# led_RGB_esp32_schematic.net
KiCad netlist of a schematic drawn in Altium Designer
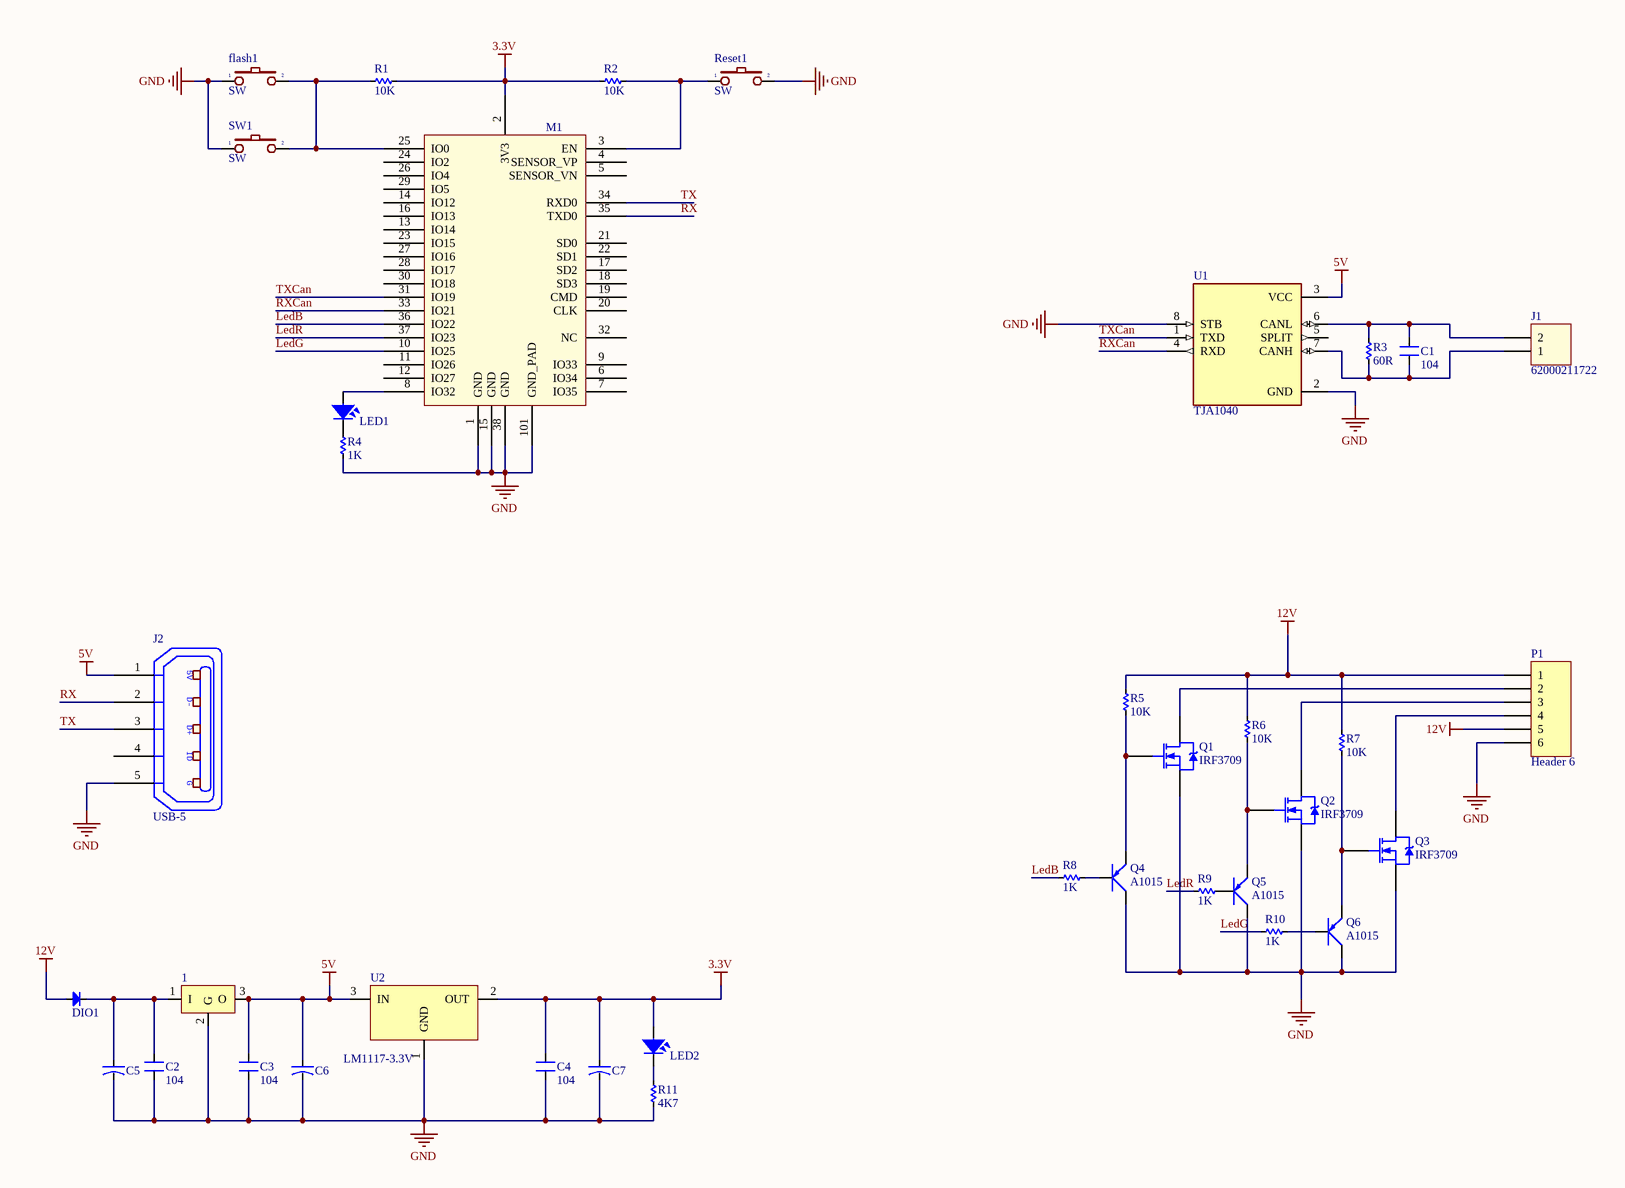
[diagram p0: led_RGB_esp32_schematic.SchDoc]

(export (version "E")
  (design (tool "Eeschema 10.0.6"))
  (components
    (comp (ref "1")
      (value "LM78xx")
      (footprint "TO252-123")
      (description "Positive Voltage Regulator")
      (fields (field (name "PUBLISHER") "Altium Limited"))
      (libsource (lib "LIBRARY") (part "LM78xx"))
    )
    (comp (ref "C1")
      (value "104")
      (footprint "SM-CAP-0805")
      (fields (field (name "DESIGNED BY") "VanDungEvn"))
      (libsource (lib "electronicvn-library1") (part "CN"))
    )
    (comp (ref "C2")
      (value "104")
      (footprint "SM-CAP-0805")
      (fields (field (name "DESIGNED BY") "VanDungEvn"))
      (libsource (lib "electronicvn-library1") (part "CN"))
    )
    (comp (ref "C3")
      (value "104")
      (footprint "SM-CAP-0805")
      (fields (field (name "DESIGNED BY") "VanDungEvn"))
      (libsource (lib "electronicvn-library1") (part "CN"))
    )
    (comp (ref "C4")
      (value "104")
      (footprint "SM-CAP-0805")
      (fields (field (name "DESIGNED BY") "VanDungEvn"))
      (libsource (lib "electronicvn-library1") (part "CN"))
    )
    (comp (ref "C5")
      (value "CN-ALU-SMD")
      (footprint "CAP-ALU-SMD-4.5x5x1.4")
      (description "Polarized Capacitor (Axial)")
      (fields (field (name "PUBLISHER") "Altium Limited"))
      (libsource (lib "LIBTanCN") (part "CN-ALU-SMD"))
    )
    (comp (ref "C6")
      (value "CN-ALU-SMD")
      (footprint "CAP-ALU-SMD-4.5x5x1.4")
      (description "Polarized Capacitor (Axial)")
      (fields (field (name "PUBLISHER") "Altium Limited"))
      (libsource (lib "LIBTanCN") (part "CN-ALU-SMD"))
    )
    (comp (ref "C7")
      (value "CN-ALU-SMD")
      (footprint "CAP-ALU-SMD-4.5x5x1.4")
      (description "Polarized Capacitor (Axial)")
      (fields (field (name "PUBLISHER") "Altium Limited"))
      (libsource (lib "LIBTanCN") (part "CN-ALU-SMD"))
    )
    (comp (ref "DIO1")
      (value "Diode SMD")
      (footprint "DIO-SMD-106")
      (description "Default Diode")
      (fields (field (name "PUBLISHER") "Altium Limited"))
      (libsource (lib "LIBRARY") (part "Diode SMD"))
    )
    (comp (ref "flash1")
      (value "SW")
      (footprint "SW-DIP1-1")
      (description "Switch button 2 pin")
      (libsource (lib "LIBRARY") (part "SW2"))
    )
    (comp (ref "J1")
      (value "62000211722")
      (footprint "62000211722")
      (description "WR-WTB 2.00mm Male Horizontal Shrouded Header, 2p")
      (fields (field (name "PUBLISHER") "Wurth Elektronik"))
      (libsource (lib "Header2.0") (part "62000211722"))
    )
    (comp (ref "J2")
      (value "USB-5")
      (footprint "USB-M1")
      (fields
        (field (name "MANUFACTURER") "FCI")
        (field (name "MANUFACTURER PART NUMBER") "10118193-0001LF")
        (field (name ".CREATOR") "MM")
        (field (name ".CHECKED PCB") "RF")
        (field (name ".CHECKED SCH") "MM")
      )
      (libsource (lib "LIBRARY") (part "USB-5"))
    )
    (comp (ref "LED1") (value "LED") (footprint "LED-0805-Blue") (libsource (lib "LIBRARY") (part "LED SMD")))
    (comp (ref "LED2") (value "LED") (footprint "LED-0805-Blue") (libsource (lib "LIBRARY") (part "LED SMD")))
    (comp (ref "M1")
      (value "ESP32S_Module")
      (footprint "ESP32S")
      (description "Esp-32S")
      (libsource (lib "ESP32S") (part "ESP32S_Module"))
    )
    (comp (ref "P1")
      (value "Header 6")
      (footprint "HED6T")
      (description "Header, 6-Pin")
      (fields (field (name "PUBLISHER") "Altium Limited"))
      (libsource (lib "LIBTanCN") (part "Header 6"))
    )
    (comp (ref "Q1")
      (value "IRF3709")
      (footprint "D2PAK_N")
      (description "HEXFET N-Channel Power MOSFET")
      (fields (field (name "PUBLISHER") "Altium Limited"))
      (libsource (lib "IR Discrete MOSFET - Power") (part "IRF540S"))
    )
    (comp (ref "Q2")
      (value "IRF3709")
      (footprint "D2PAK_N")
      (description "HEXFET N-Channel Power MOSFET")
      (fields (field (name "PUBLISHER") "Altium Limited"))
      (libsource (lib "IR Discrete MOSFET - Power") (part "IRF540S"))
    )
    (comp (ref "Q3")
      (value "IRF3709")
      (footprint "D2PAK_N")
      (description "HEXFET N-Channel Power MOSFET")
      (fields (field (name "PUBLISHER") "Altium Limited"))
      (libsource (lib "IR Discrete MOSFET - Power") (part "IRF540S"))
    )
    (comp (ref "Q4")
      (value "A1015")
      (footprint "SOT23B")
      (description "PNP 600mW, ECB")
      (libsource (lib "electronicvn-library1") (part "A1015"))
    )
    (comp (ref "Q5")
      (value "A1015")
      (footprint "SOT23B")
      (description "PNP 600mW, ECB")
      (libsource (lib "electronicvn-library1") (part "A1015"))
    )
    (comp (ref "Q6")
      (value "A1015")
      (footprint "SOT23B")
      (description "PNP 600mW, ECB")
      (libsource (lib "electronicvn-library1") (part "A1015"))
    )
    (comp (ref "R1")
      (value "10K")
      (footprint "RES-SMD-0805")
      (description "Resistor")
      (fields
        (field (name "MANUFACTURER") "Generic Components")
        (field (name "PUBLISHER") "Altium Hobart Technology Centre")
      )
      (libsource (lib "LIBRARY") (part "Res-SMD"))
    )
    (comp (ref "R2")
      (value "10K")
      (footprint "RES-SMD-0805")
      (description "Resistor")
      (fields
        (field (name "MANUFACTURER") "Generic Components")
        (field (name "PUBLISHER") "Altium Hobart Technology Centre")
      )
      (libsource (lib "LIBRARY") (part "Res-SMD"))
    )
    (comp (ref "R3")
      (value "60R")
      (footprint "RES-SMD-0805")
      (description "Resistor")
      (fields
        (field (name "MANUFACTURER") "Generic Components")
        (field (name "PUBLISHER") "Altium Hobart Technology Centre")
      )
      (libsource (lib "LIBRARY") (part "Res-SMD"))
    )
    (comp (ref "R4")
      (value "1K")
      (footprint "RES-SMD-0805")
      (description "Resistor")
      (fields
        (field (name "MANUFACTURER") "Generic Components")
        (field (name "PUBLISHER") "Altium Hobart Technology Centre")
      )
      (libsource (lib "LIBRARY") (part "Res-SMD"))
    )
    (comp (ref "R5")
      (value "10K")
      (footprint "RES-SMD-0805")
      (description "Resistor")
      (fields
        (field (name "MANUFACTURER") "Generic Components")
        (field (name "PUBLISHER") "Altium Hobart Technology Centre")
      )
      (libsource (lib "LIBRARY") (part "Res-SMD"))
    )
    (comp (ref "R6")
      (value "10K")
      (footprint "RES-SMD-0805")
      (description "Resistor")
      (fields
        (field (name "MANUFACTURER") "Generic Components")
        (field (name "PUBLISHER") "Altium Hobart Technology Centre")
      )
      (libsource (lib "LIBRARY") (part "Res-SMD"))
    )
    (comp (ref "R7")
      (value "10K")
      (footprint "RES-SMD-0805")
      (description "Resistor")
      (fields
        (field (name "MANUFACTURER") "Generic Components")
        (field (name "PUBLISHER") "Altium Hobart Technology Centre")
      )
      (libsource (lib "LIBRARY") (part "Res-SMD"))
    )
    (comp (ref "R8")
      (value "1K")
      (footprint "RES-SMD-0805")
      (description "Resistor")
      (fields
        (field (name "MANUFACTURER") "Generic Components")
        (field (name "PUBLISHER") "Altium Hobart Technology Centre")
      )
      (libsource (lib "LIBRARY") (part "Res-SMD"))
    )
    (comp (ref "R9")
      (value "1K")
      (footprint "RES-SMD-0805")
      (description "Resistor")
      (fields
        (field (name "MANUFACTURER") "Generic Components")
        (field (name "PUBLISHER") "Altium Hobart Technology Centre")
      )
      (libsource (lib "LIBRARY") (part "Res-SMD"))
    )
    (comp (ref "R10")
      (value "1K")
      (footprint "RES-SMD-0805")
      (description "Resistor")
      (fields
        (field (name "MANUFACTURER") "Generic Components")
        (field (name "PUBLISHER") "Altium Hobart Technology Centre")
      )
      (libsource (lib "LIBRARY") (part "Res-SMD"))
    )
    (comp (ref "R11")
      (value "4K7")
      (footprint "RES-SMD-0805")
      (description "Resistor")
      (fields
        (field (name "MANUFACTURER") "Generic Components")
        (field (name "PUBLISHER") "Altium Hobart Technology Centre")
      )
      (libsource (lib "LIBRARY") (part "Res-SMD"))
    )
    (comp (ref "Reset1")
      (value "SW")
      (footprint "SW1-SMD")
      (description "Switch button 2 pin")
      (libsource (lib "LIBRARY") (part "SW2"))
    )
    (comp (ref "SW1")
      (value "SW")
      (footprint "SW2-D2")
      (description "Switch button 2 pin")
      (libsource (lib "LIBTanCN") (part "SW2"))
    )
    (comp (ref "U1")
      (value "TJA1040")
      (footprint "SOIC127P600X175-8N")
      (description "1/1 Transceiver Half CANbus 8-SO")
      (fields (field (name "MF") "NXP USA"))
      (libsource (lib "TJA1040") (part "TJA1040"))
    )
    (comp (ref "U2")
      (value "LM1117-3.3V")
      (footprint "SOT223")
      (description "800mA Low-Dropout Linear Regulator")
      (fields (field (name "CREATOR") "Nguyen Ba Bien"))
      (libsource (lib "LIBRARY") (part "LM1117"))
    )
  )
  (nets
    (net (code "1") (name "/LedB") (class "Default")
      (node (ref "M1") (pin "36") (pinfunction "IO22_36") (pintype "passive"))
      (node (ref "R8") (pin "1") (pinfunction "1_1") (pintype "passive"))
    )
    (net (code "2") (name "/LedG") (class "Default")
      (node (ref "M1") (pin "10") (pinfunction "IO25_10") (pintype "passive"))
      (node (ref "R10") (pin "1") (pinfunction "1_1") (pintype "passive"))
    )
    (net (code "3") (name "/LedR") (class "Default")
      (node (ref "M1") (pin "37") (pinfunction "IO23_37") (pintype "passive"))
      (node (ref "R9") (pin "1") (pinfunction "1_1") (pintype "passive"))
    )
    (net (code "4") (name "/RX") (class "Default")
      (node (ref "J2") (pin "2") (pinfunction "P2_2") (pintype "passive"))
      (node (ref "M1") (pin "35") (pinfunction "TXD0_35") (pintype "passive"))
    )
    (net (code "5") (name "/RXCan") (class "Default")
      (node (ref "M1") (pin "33") (pinfunction "IO21_33") (pintype "passive"))
      (node (ref "U1") (pin "4") (pinfunction "RXD_4") (pintype "output"))
    )
    (net (code "6") (name "/TX") (class "Default")
      (node (ref "J2") (pin "3") (pinfunction "P3_3") (pintype "passive"))
      (node (ref "M1") (pin "34") (pinfunction "RXD0_34") (pintype "passive"))
    )
    (net (code "7") (name "/TXCan") (class "Default")
      (node (ref "M1") (pin "31") (pinfunction "IO19_31") (pintype "passive"))
      (node (ref "U1") (pin "1") (pinfunction "TXD_1") (pintype "input"))
    )
    (net (code "8") (name "3.3V") (class "Default")
      (node (ref "C4") (pin "2") (pinfunction "2_2") (pintype "passive"))
      (node (ref "C7") (pin "1") (pinfunction "1_1") (pintype "passive"))
      (node (ref "LED2") (pin "1") (pinfunction "1_1") (pintype "passive"))
      (node (ref "M1") (pin "2") (pinfunction "3V3_2") (pintype "power_in"))
      (node (ref "R1") (pin "2") (pinfunction "2_2") (pintype "passive"))
      (node (ref "R2") (pin "1") (pinfunction "1_1") (pintype "passive"))
      (node (ref "U2") (pin "2") (pinfunction "OUT_2") (pintype "passive"))
    )
    (net (code "9") (name "5V") (class "Default")
      (node (ref "1") (pin "3") (pinfunction "O_3") (pintype "power_in"))
      (node (ref "C3") (pin "2") (pinfunction "2_2") (pintype "passive"))
      (node (ref "C6") (pin "1") (pinfunction "1_1") (pintype "passive"))
      (node (ref "J2") (pin "1") (pinfunction "P1_1") (pintype "passive"))
      (node (ref "U1") (pin "3") (pinfunction "VCC_3") (pintype "power_in"))
      (node (ref "U2") (pin "3") (pinfunction "IN_3") (pintype "passive"))
    )
    (net (code "10") (name "12V") (class "Default")
      (node (ref "DIO1") (pin "1") (pinfunction "A_1") (pintype "passive"))
      (node (ref "P1") (pin "1") (pinfunction "1_1") (pintype "passive"))
      (node (ref "P1") (pin "5") (pinfunction "5_5") (pintype "passive"))
      (node (ref "R5") (pin "1") (pinfunction "1_1") (pintype "passive"))
      (node (ref "R6") (pin "1") (pinfunction "1_1") (pintype "passive"))
      (node (ref "R7") (pin "1") (pinfunction "1_1") (pintype "passive"))
    )
    (net (code "11") (name "GND") (class "Default")
      (node (ref "1") (pin "2") (pinfunction "G_2") (pintype "power_in"))
      (node (ref "C2") (pin "1") (pinfunction "1_1") (pintype "passive"))
      (node (ref "C3") (pin "1") (pinfunction "1_1") (pintype "passive"))
      (node (ref "C4") (pin "1") (pinfunction "1_1") (pintype "passive"))
      (node (ref "C5") (pin "2") (pinfunction "2_2") (pintype "passive"))
      (node (ref "C6") (pin "2") (pinfunction "2_2") (pintype "passive"))
      (node (ref "C7") (pin "2") (pinfunction "2_2") (pintype "passive"))
      (node (ref "J2") (pin "5") (pinfunction "P5_5") (pintype "passive"))
      (node (ref "M1") (pin "1") (pinfunction "GND_1") (pintype "power_in"))
      (node (ref "M1") (pin "101") (pinfunction "GND_PAD_101") (pintype "power_in"))
      (node (ref "M1") (pin "15") (pinfunction "GND_15") (pintype "power_in"))
      (node (ref "M1") (pin "38") (pinfunction "GND_38") (pintype "power_in"))
      (node (ref "P1") (pin "6") (pinfunction "6_6") (pintype "passive"))
      (node (ref "Q1") (pin "3") (pinfunction "S_3") (pintype "passive"))
      (node (ref "Q2") (pin "3") (pinfunction "S_3") (pintype "passive"))
      (node (ref "Q3") (pin "3") (pinfunction "S_3") (pintype "passive"))
      (node (ref "Q4") (pin "2") (pinfunction "C_2") (pintype "passive"))
      (node (ref "Q5") (pin "2") (pinfunction "C_2") (pintype "passive"))
      (node (ref "Q6") (pin "2") (pinfunction "C_2") (pintype "passive"))
      (node (ref "R11") (pin "2") (pinfunction "2_2") (pintype "passive"))
      (node (ref "R4") (pin "1") (pinfunction "1_1") (pintype "passive"))
      (node (ref "Reset1") (pin "2") (pinfunction "2_2") (pintype "passive"))
      (node (ref "SW1") (pin "1") (pinfunction "1_1") (pintype "passive"))
      (node (ref "U1") (pin "2") (pinfunction "GND_2") (pintype "power_in"))
      (node (ref "U1") (pin "8") (pinfunction "STB_8") (pintype "input"))
      (node (ref "U2") (pin "1") (pinfunction "GND_1") (pintype "passive"))
      (node (ref "flash1") (pin "1") (pinfunction "1_1") (pintype "passive"))
    )
    (net (code "12") (name "Net-(1-I)") (class "Default")
      (node (ref "1") (pin "1") (pinfunction "I_1") (pintype "power_in"))
      (node (ref "C2") (pin "2") (pinfunction "2_2") (pintype "passive"))
      (node (ref "C5") (pin "1") (pinfunction "1_1") (pintype "passive"))
      (node (ref "DIO1") (pin "2") (pinfunction "K_2") (pintype "passive"))
    )
    (net (code "13") (name "Net-(LED1-Pad2)") (class "Default")
      (node (ref "LED1") (pin "2") (pinfunction "2_2") (pintype "passive"))
      (node (ref "R4") (pin "2") (pinfunction "2_2") (pintype "passive"))
    )
    (net (code "14") (name "Net-(LED2-Pad2)") (class "Default")
      (node (ref "LED2") (pin "2") (pinfunction "2_2") (pintype "passive"))
      (node (ref "R11") (pin "1") (pinfunction "1_1") (pintype "passive"))
    )
    (net (code "15") (name "Net-(M1-EN)") (class "Default")
      (node (ref "M1") (pin "3") (pinfunction "EN_3") (pintype "power_in"))
      (node (ref "R2") (pin "2") (pinfunction "2_2") (pintype "passive"))
      (node (ref "Reset1") (pin "1") (pinfunction "1_1") (pintype "passive"))
    )
    (net (code "16") (name "Net-(M1-IO0)") (class "Default")
      (node (ref "M1") (pin "25") (pinfunction "IO0_25") (pintype "passive"))
      (node (ref "R1") (pin "1") (pinfunction "1_1") (pintype "passive"))
      (node (ref "SW1") (pin "2") (pinfunction "2_2") (pintype "passive"))
      (node (ref "flash1") (pin "2") (pinfunction "2_2") (pintype "passive"))
    )
    (net (code "17") (name "Net-(M1-IO32)") (class "Default")
      (node (ref "LED1") (pin "1") (pinfunction "1_1") (pintype "passive"))
      (node (ref "M1") (pin "8") (pinfunction "IO32_8") (pintype "passive"))
    )
    (net (code "18") (name "Net-(Q1-D)") (class "Default")
      (node (ref "P1") (pin "2") (pinfunction "2_2") (pintype "passive"))
      (node (ref "Q1") (pin "2") (pinfunction "D_2") (pintype "passive"))
    )
    (net (code "19") (name "Net-(Q1-G)") (class "Default")
      (node (ref "Q1") (pin "1") (pinfunction "G_1") (pintype "passive"))
      (node (ref "Q4") (pin "1") (pinfunction "E_1") (pintype "passive"))
      (node (ref "R5") (pin "2") (pinfunction "2_2") (pintype "passive"))
    )
    (net (code "20") (name "Net-(Q2-D)") (class "Default")
      (node (ref "P1") (pin "3") (pinfunction "3_3") (pintype "passive"))
      (node (ref "Q2") (pin "2") (pinfunction "D_2") (pintype "passive"))
    )
    (net (code "21") (name "Net-(Q2-G)") (class "Default")
      (node (ref "Q2") (pin "1") (pinfunction "G_1") (pintype "passive"))
      (node (ref "Q5") (pin "1") (pinfunction "E_1") (pintype "passive"))
      (node (ref "R6") (pin "2") (pinfunction "2_2") (pintype "passive"))
    )
    (net (code "22") (name "Net-(Q3-D)") (class "Default")
      (node (ref "P1") (pin "4") (pinfunction "4_4") (pintype "passive"))
      (node (ref "Q3") (pin "2") (pinfunction "D_2") (pintype "passive"))
    )
    (net (code "23") (name "Net-(Q3-G)") (class "Default")
      (node (ref "Q3") (pin "1") (pinfunction "G_1") (pintype "passive"))
      (node (ref "Q6") (pin "1") (pinfunction "E_1") (pintype "passive"))
      (node (ref "R7") (pin "2") (pinfunction "2_2") (pintype "passive"))
    )
    (net (code "24") (name "Net-(Q4-B)") (class "Default")
      (node (ref "Q4") (pin "3") (pinfunction "B_3") (pintype "passive"))
      (node (ref "R8") (pin "2") (pinfunction "2_2") (pintype "passive"))
    )
    (net (code "25") (name "Net-(Q5-B)") (class "Default")
      (node (ref "Q5") (pin "3") (pinfunction "B_3") (pintype "passive"))
      (node (ref "R9") (pin "2") (pinfunction "2_2") (pintype "passive"))
    )
    (net (code "26") (name "Net-(Q6-B)") (class "Default")
      (node (ref "Q6") (pin "3") (pinfunction "B_3") (pintype "passive"))
      (node (ref "R10") (pin "2") (pinfunction "2_2") (pintype "passive"))
    )
    (net (code "27") (name "Net-(U1-CANH)") (class "Default")
      (node (ref "C1") (pin "1") (pinfunction "1_1") (pintype "passive"))
      (node (ref "J1") (pin "1") (pinfunction "1_1") (pintype "passive"))
      (node (ref "R3") (pin "1") (pinfunction "1_1") (pintype "passive"))
      (node (ref "U1") (pin "7") (pinfunction "CANH_7") (pintype "bidirectional"))
    )
    (net (code "28") (name "Net-(U1-CANL)") (class "Default")
      (node (ref "C1") (pin "2") (pinfunction "2_2") (pintype "passive"))
      (node (ref "J1") (pin "2") (pinfunction "2_2") (pintype "passive"))
      (node (ref "R3") (pin "2") (pinfunction "2_2") (pintype "passive"))
      (node (ref "U1") (pin "6") (pinfunction "CANL_6") (pintype "bidirectional"))
    )
    (net (code "29") (name "unconnected-(J2-P4-Pad4)") (class "Default")
      (node (ref "J2") (pin "4") (pinfunction "P4_4") (pintype "passive"))
    )
    (net (code "30") (name "unconnected-(M1-CLK-Pad20)") (class "Default")
      (node (ref "M1") (pin "20") (pinfunction "CLK_20") (pintype "passive"))
    )
    (net (code "31") (name "unconnected-(M1-CMD-Pad19)") (class "Default")
      (node (ref "M1") (pin "19") (pinfunction "CMD_19") (pintype "passive"))
    )
    (net (code "32") (name "unconnected-(M1-IO2-Pad24)") (class "Default")
      (node (ref "M1") (pin "24") (pinfunction "IO2_24") (pintype "passive"))
    )
    (net (code "33") (name "unconnected-(M1-IO4-Pad26)") (class "Default")
      (node (ref "M1") (pin "26") (pinfunction "IO4_26") (pintype "passive"))
    )
    (net (code "34") (name "unconnected-(M1-IO5-Pad29)") (class "Default")
      (node (ref "M1") (pin "29") (pinfunction "IO5_29") (pintype "passive"))
    )
    (net (code "35") (name "unconnected-(M1-IO12-Pad14)") (class "Default")
      (node (ref "M1") (pin "14") (pinfunction "IO12_14") (pintype "passive"))
    )
    (net (code "36") (name "unconnected-(M1-IO13-Pad16)") (class "Default")
      (node (ref "M1") (pin "16") (pinfunction "IO13_16") (pintype "passive"))
    )
    (net (code "37") (name "unconnected-(M1-IO14-Pad13)") (class "Default")
      (node (ref "M1") (pin "13") (pinfunction "IO14_13") (pintype "passive"))
    )
    (net (code "38") (name "unconnected-(M1-IO15-Pad23)") (class "Default")
      (node (ref "M1") (pin "23") (pinfunction "IO15_23") (pintype "passive"))
    )
    (net (code "39") (name "unconnected-(M1-IO16-Pad27)") (class "Default")
      (node (ref "M1") (pin "27") (pinfunction "IO16_27") (pintype "passive"))
    )
    (net (code "40") (name "unconnected-(M1-IO17-Pad28)") (class "Default")
      (node (ref "M1") (pin "28") (pinfunction "IO17_28") (pintype "passive"))
    )
    (net (code "41") (name "unconnected-(M1-IO18-Pad30)") (class "Default")
      (node (ref "M1") (pin "30") (pinfunction "IO18_30") (pintype "passive"))
    )
    (net (code "42") (name "unconnected-(M1-IO26-Pad11)") (class "Default")
      (node (ref "M1") (pin "11") (pinfunction "IO26_11") (pintype "passive"))
    )
    (net (code "43") (name "unconnected-(M1-IO27-Pad12)") (class "Default")
      (node (ref "M1") (pin "12") (pinfunction "IO27_12") (pintype "passive"))
    )
    (net (code "44") (name "unconnected-(M1-IO33-Pad9)") (class "Default")
      (node (ref "M1") (pin "9") (pinfunction "IO33_9") (pintype "passive"))
    )
    (net (code "45") (name "unconnected-(M1-IO34-Pad6)") (class "Default")
      (node (ref "M1") (pin "6") (pinfunction "IO34_6") (pintype "passive"))
    )
    (net (code "46") (name "unconnected-(M1-IO35-Pad7)") (class "Default")
      (node (ref "M1") (pin "7") (pinfunction "IO35_7") (pintype "passive"))
    )
    (net (code "47") (name "unconnected-(M1-NC-Pad32)") (class "Default")
      (node (ref "M1") (pin "32") (pinfunction "NC_32") (pintype "passive"))
    )
    (net (code "48") (name "unconnected-(M1-SD0-Pad21)") (class "Default")
      (node (ref "M1") (pin "21") (pinfunction "SD0_21") (pintype "passive"))
    )
    (net (code "49") (name "unconnected-(M1-SD1-Pad22)") (class "Default")
      (node (ref "M1") (pin "22") (pinfunction "SD1_22") (pintype "passive"))
    )
    (net (code "50") (name "unconnected-(M1-SD2-Pad17)") (class "Default")
      (node (ref "M1") (pin "17") (pinfunction "SD2_17") (pintype "passive"))
    )
    (net (code "51") (name "unconnected-(M1-SD3-Pad18)") (class "Default")
      (node (ref "M1") (pin "18") (pinfunction "SD3_18") (pintype "passive"))
    )
    (net (code "52") (name "unconnected-(M1-SENSOR_VN-Pad5)") (class "Default")
      (node (ref "M1") (pin "5") (pinfunction "SENSOR_VN_5") (pintype "passive"))
    )
    (net (code "53") (name "unconnected-(M1-SENSOR_VP-Pad4)") (class "Default")
      (node (ref "M1") (pin "4") (pinfunction "SENSOR_VP_4") (pintype "passive"))
    )
    (net (code "54") (name "unconnected-(U1-SPLIT-Pad5)") (class "Default")
      (node (ref "U1") (pin "5") (pinfunction "SPLIT_5") (pintype "output"))
    )
  )
)
